# alu.net
KiCad netlist of a schematic drawn in EAGLE
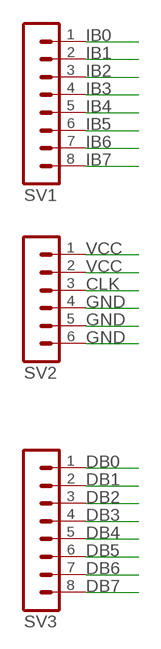
[diagram p0: schematic, sheet 1, part 1 of 2]
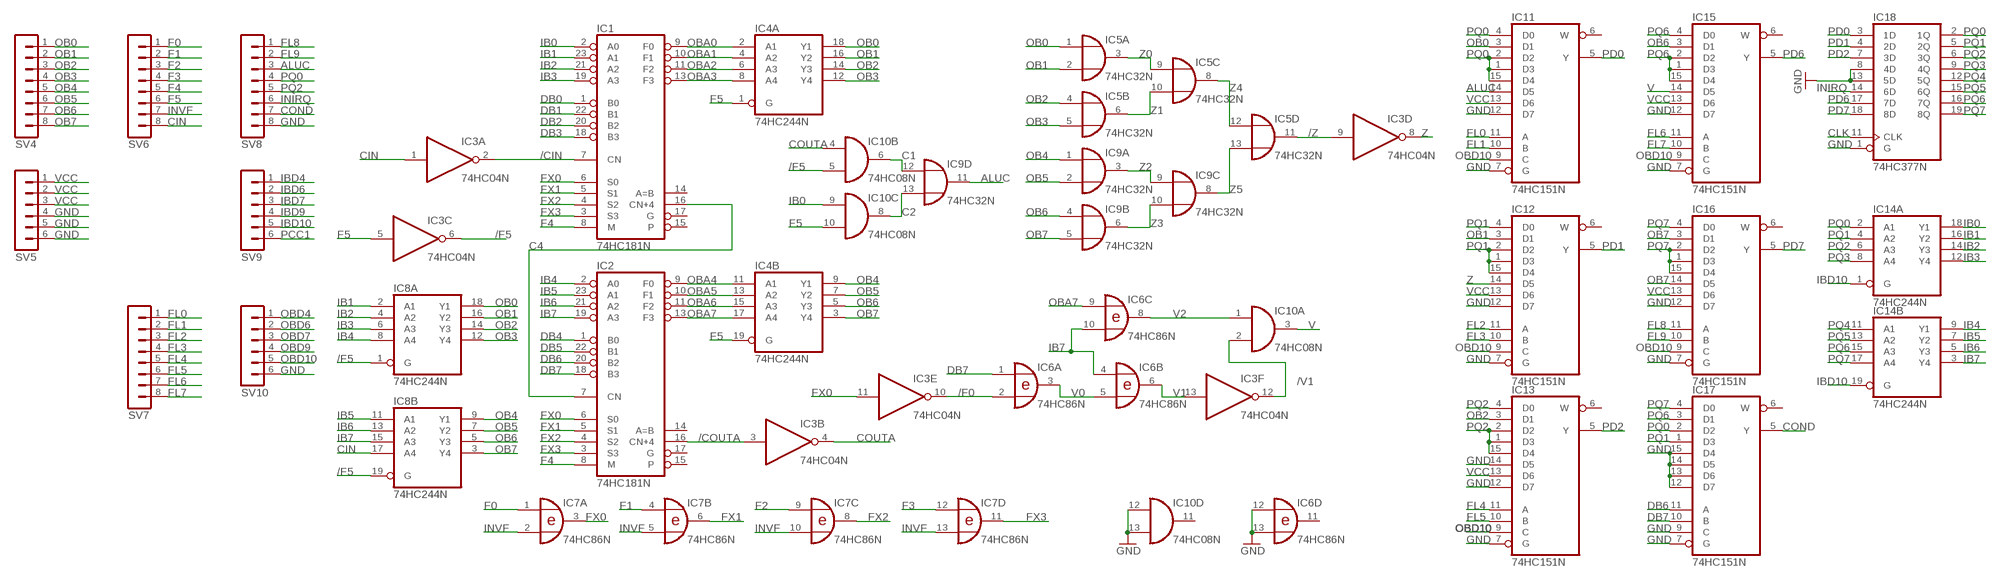
[diagram p1: schematic, sheet 1, part 2 of 2]

(export (version "E")
  (design (tool "Eeschema 10.0.6"))
  (components
    (comp (ref "IC1")
      (value "74HC181N")
      (footprint "eagle-import:DIL24-6")
      (libsource (lib "eagle-import") (part "74181NHC"))
    )
    (comp (ref "IC2")
      (value "74HC181N")
      (footprint "eagle-import:DIL24-6")
      (libsource (lib "eagle-import") (part "74181NHC"))
    )
    (comp (ref "IC3")
      (value "74HC04N")
      (footprint "eagle-import:DIL14")
      (libsource (lib "eagle-import") (part "7404NHC"))
    )
    (comp (ref "IC4")
      (value "74HC244N")
      (footprint "eagle-import:DIL20")
      (libsource (lib "eagle-import") (part "74244NHC"))
    )
    (comp (ref "IC5")
      (value "74HC32N")
      (footprint "eagle-import:DIL14")
      (libsource (lib "eagle-import") (part "7432NHC"))
    )
    (comp (ref "IC6")
      (value "74HC86N")
      (footprint "eagle-import:DIL14")
      (libsource (lib "eagle-import") (part "7486NHC"))
    )
    (comp (ref "IC7")
      (value "74HC86N")
      (footprint "eagle-import:DIL14")
      (libsource (lib "eagle-import") (part "7486NHC"))
    )
    (comp (ref "IC8")
      (value "74HC244N")
      (footprint "eagle-import:DIL20")
      (libsource (lib "eagle-import") (part "74244NHC"))
    )
    (comp (ref "IC9")
      (value "74HC32N")
      (footprint "eagle-import:DIL14")
      (libsource (lib "eagle-import") (part "7432NHC"))
    )
    (comp (ref "IC10")
      (value "74HC08N")
      (footprint "eagle-import:DIL14")
      (libsource (lib "eagle-import") (part "7408NHC"))
    )
    (comp (ref "IC11")
      (value "74HC151N")
      (footprint "eagle-import:DIL16")
      (libsource (lib "eagle-import") (part "74151NHC"))
    )
    (comp (ref "IC12")
      (value "74HC151N")
      (footprint "eagle-import:DIL16")
      (libsource (lib "eagle-import") (part "74151NHC"))
    )
    (comp (ref "IC13")
      (value "74HC151N")
      (footprint "eagle-import:DIL16")
      (libsource (lib "eagle-import") (part "74151NHC"))
    )
    (comp (ref "IC14")
      (value "74HC244N")
      (footprint "eagle-import:DIL20")
      (libsource (lib "eagle-import") (part "74244NHC"))
    )
    (comp (ref "IC15")
      (value "74HC151N")
      (footprint "eagle-import:DIL16")
      (libsource (lib "eagle-import") (part "74151NHC"))
    )
    (comp (ref "IC16")
      (value "74HC151N")
      (footprint "eagle-import:DIL16")
      (libsource (lib "eagle-import") (part "74151NHC"))
    )
    (comp (ref "IC17")
      (value "74HC151N")
      (footprint "eagle-import:DIL16")
      (libsource (lib "eagle-import") (part "74151NHC"))
    )
    (comp (ref "IC18")
      (value "74HC377N")
      (footprint "eagle-import:DIL20")
      (libsource (lib "eagle-import") (part "74377NHC"))
    )
    (comp (ref "SV1")
      (value "MA08-1")
      (footprint "eagle-import:MA08-1")
      (libsource (lib "eagle-import") (part "MA08-1"))
    )
    (comp (ref "SV2")
      (value "MA06-1")
      (footprint "eagle-import:MA06-1")
      (libsource (lib "eagle-import") (part "MA06-1"))
    )
    (comp (ref "SV3")
      (value "MA08-1")
      (footprint "eagle-import:MA08-1")
      (libsource (lib "eagle-import") (part "MA08-1"))
    )
    (comp (ref "SV4")
      (value "MA08-1")
      (footprint "eagle-import:MA08-1")
      (libsource (lib "eagle-import") (part "MA08-1"))
    )
    (comp (ref "SV5")
      (value "MA06-1")
      (footprint "eagle-import:MA06-1")
      (libsource (lib "eagle-import") (part "MA06-1"))
    )
    (comp (ref "SV6")
      (value "MA08-1")
      (footprint "eagle-import:MA08-1")
      (libsource (lib "eagle-import") (part "MA08-1"))
    )
    (comp (ref "SV7")
      (value "MA08-1")
      (footprint "eagle-import:MA08-1")
      (libsource (lib "eagle-import") (part "MA08-1"))
    )
    (comp (ref "SV8")
      (value "MA08-1")
      (footprint "eagle-import:MA08-1")
      (libsource (lib "eagle-import") (part "MA08-1"))
    )
    (comp (ref "SV9")
      (value "MA06-1")
      (footprint "eagle-import:MA06-1")
      (libsource (lib "eagle-import") (part "MA06-1"))
    )
    (comp (ref "SV10")
      (value "MA06-1")
      (footprint "eagle-import:MA06-1")
      (libsource (lib "eagle-import") (part "MA06-1"))
    )
  )
  (nets
    (net (code "1") (name "/ALUC") (class "Default")
      (node (ref "IC11") (pin "14") (pinfunction "D5_14") (pintype "input"))
      (node (ref "IC9") (pin "11") (pinfunction "O_11") (pintype "output"))
      (node (ref "SV8") (pin "3") (pinfunction "3_3") (pintype "passive"))
    )
    (net (code "2") (name "/C1") (class "Default")
      (node (ref "IC10") (pin "6") (pinfunction "O_6") (pintype "output"))
      (node (ref "IC9") (pin "12") (pinfunction "I0_12") (pintype "input"))
    )
    (net (code "3") (name "/C2") (class "Default")
      (node (ref "IC10") (pin "8") (pinfunction "O_8") (pintype "output"))
      (node (ref "IC9") (pin "13") (pinfunction "I1_13") (pintype "input"))
    )
    (net (code "4") (name "/C4") (class "Default")
      (node (ref "IC1") (pin "16") (pinfunction "CN+4_16") (pintype "output"))
      (node (ref "IC2") (pin "7") (pinfunction "CN_7") (pintype "input"))
    )
    (net (code "5") (name "/CIN") (class "Default")
      (node (ref "IC3") (pin "1") (pinfunction "I_1") (pintype "input"))
      (node (ref "IC8") (pin "17") (pinfunction "A4_17") (pintype "input"))
      (node (ref "SV6") (pin "8") (pinfunction "8_8") (pintype "passive"))
    )
    (net (code "6") (name "/CLK") (class "Default")
      (node (ref "IC18") (pin "11") (pinfunction "CLK_11") (pintype "input"))
      (node (ref "SV2") (pin "3") (pinfunction "3_3") (pintype "passive"))
    )
    (net (code "7") (name "/COND") (class "Default")
      (node (ref "IC17") (pin "5") (pinfunction "Y_5") (pintype "output"))
      (node (ref "SV8") (pin "7") (pinfunction "7_7") (pintype "passive"))
    )
    (net (code "8") (name "/COUTA") (class "Default")
      (node (ref "IC10") (pin "4") (pinfunction "I0_4") (pintype "input"))
      (node (ref "IC3") (pin "4") (pinfunction "O_4") (pintype "output"))
    )
    (net (code "9") (name "/DB0") (class "Default")
      (node (ref "IC1") (pin "1") (pinfunction "B0_1") (pintype "input"))
      (node (ref "SV3") (pin "1") (pinfunction "1_1") (pintype "passive"))
    )
    (net (code "10") (name "/DB1") (class "Default")
      (node (ref "IC1") (pin "22") (pinfunction "B1_22") (pintype "input"))
      (node (ref "SV3") (pin "2") (pinfunction "2_2") (pintype "passive"))
    )
    (net (code "11") (name "/DB2") (class "Default")
      (node (ref "IC1") (pin "20") (pinfunction "B2_20") (pintype "input"))
      (node (ref "SV3") (pin "3") (pinfunction "3_3") (pintype "passive"))
    )
    (net (code "12") (name "/DB3") (class "Default")
      (node (ref "IC1") (pin "18") (pinfunction "B3_18") (pintype "input"))
      (node (ref "SV3") (pin "4") (pinfunction "4_4") (pintype "passive"))
    )
    (net (code "13") (name "/DB4") (class "Default")
      (node (ref "IC2") (pin "1") (pinfunction "B0_1") (pintype "input"))
      (node (ref "SV3") (pin "5") (pinfunction "5_5") (pintype "passive"))
    )
    (net (code "14") (name "/DB5") (class "Default")
      (node (ref "IC2") (pin "22") (pinfunction "B1_22") (pintype "input"))
      (node (ref "SV3") (pin "6") (pinfunction "6_6") (pintype "passive"))
    )
    (net (code "15") (name "/DB6") (class "Default")
      (node (ref "IC17") (pin "11") (pinfunction "A_11") (pintype "input"))
      (node (ref "IC2") (pin "20") (pinfunction "B2_20") (pintype "input"))
      (node (ref "SV3") (pin "7") (pinfunction "7_7") (pintype "passive"))
    )
    (net (code "16") (name "/DB7") (class "Default")
      (node (ref "IC17") (pin "10") (pinfunction "B_10") (pintype "input"))
      (node (ref "IC2") (pin "18") (pinfunction "B3_18") (pintype "input"))
      (node (ref "IC6") (pin "1") (pinfunction "I0_1") (pintype "input"))
      (node (ref "SV3") (pin "8") (pinfunction "8_8") (pintype "passive"))
    )
    (net (code "17") (name "/F0") (class "Default")
      (node (ref "IC7") (pin "1") (pinfunction "I0_1") (pintype "input"))
      (node (ref "SV6") (pin "1") (pinfunction "1_1") (pintype "passive"))
    )
    (net (code "18") (name "/F1") (class "Default")
      (node (ref "IC7") (pin "4") (pinfunction "I0_4") (pintype "input"))
      (node (ref "SV6") (pin "2") (pinfunction "2_2") (pintype "passive"))
    )
    (net (code "19") (name "/F2") (class "Default")
      (node (ref "IC7") (pin "9") (pinfunction "I0_9") (pintype "input"))
      (node (ref "SV6") (pin "3") (pinfunction "3_3") (pintype "passive"))
    )
    (net (code "20") (name "/F3") (class "Default")
      (node (ref "IC7") (pin "12") (pinfunction "I0_12") (pintype "input"))
      (node (ref "SV6") (pin "4") (pinfunction "4_4") (pintype "passive"))
    )
    (net (code "21") (name "/F4") (class "Default")
      (node (ref "IC1") (pin "8") (pinfunction "M_8") (pintype "input"))
      (node (ref "IC2") (pin "8") (pinfunction "M_8") (pintype "input"))
      (node (ref "SV6") (pin "5") (pinfunction "5_5") (pintype "passive"))
    )
    (net (code "22") (name "/F5") (class "Default")
      (node (ref "IC10") (pin "10") (pinfunction "I1_10") (pintype "input"))
      (node (ref "IC3") (pin "5") (pinfunction "I_5") (pintype "input"))
      (node (ref "IC4") (pin "1") (pinfunction "G_1") (pintype "input"))
      (node (ref "IC4") (pin "19") (pinfunction "G_19") (pintype "input"))
      (node (ref "SV6") (pin "6") (pinfunction "6_6") (pintype "passive"))
    )
    (net (code "23") (name "/FL0") (class "Default")
      (node (ref "IC11") (pin "11") (pinfunction "A_11") (pintype "input"))
      (node (ref "SV7") (pin "1") (pinfunction "1_1") (pintype "passive"))
    )
    (net (code "24") (name "/FL1") (class "Default")
      (node (ref "IC11") (pin "10") (pinfunction "B_10") (pintype "input"))
      (node (ref "SV7") (pin "2") (pinfunction "2_2") (pintype "passive"))
    )
    (net (code "25") (name "/FL2") (class "Default")
      (node (ref "IC12") (pin "11") (pinfunction "A_11") (pintype "input"))
      (node (ref "SV7") (pin "3") (pinfunction "3_3") (pintype "passive"))
    )
    (net (code "26") (name "/FL3") (class "Default")
      (node (ref "IC12") (pin "10") (pinfunction "B_10") (pintype "input"))
      (node (ref "SV7") (pin "4") (pinfunction "4_4") (pintype "passive"))
    )
    (net (code "27") (name "/FL4") (class "Default")
      (node (ref "IC13") (pin "11") (pinfunction "A_11") (pintype "input"))
      (node (ref "SV7") (pin "5") (pinfunction "5_5") (pintype "passive"))
    )
    (net (code "28") (name "/FL5") (class "Default")
      (node (ref "IC13") (pin "10") (pinfunction "B_10") (pintype "input"))
      (node (ref "SV7") (pin "6") (pinfunction "6_6") (pintype "passive"))
    )
    (net (code "29") (name "/FL6") (class "Default")
      (node (ref "IC15") (pin "11") (pinfunction "A_11") (pintype "input"))
      (node (ref "SV7") (pin "7") (pinfunction "7_7") (pintype "passive"))
    )
    (net (code "30") (name "/FL7") (class "Default")
      (node (ref "IC15") (pin "10") (pinfunction "B_10") (pintype "input"))
      (node (ref "SV7") (pin "8") (pinfunction "8_8") (pintype "passive"))
    )
    (net (code "31") (name "/FL8") (class "Default")
      (node (ref "IC16") (pin "11") (pinfunction "A_11") (pintype "input"))
      (node (ref "SV8") (pin "1") (pinfunction "1_1") (pintype "passive"))
    )
    (net (code "32") (name "/FL9") (class "Default")
      (node (ref "IC16") (pin "10") (pinfunction "B_10") (pintype "input"))
      (node (ref "SV8") (pin "2") (pinfunction "2_2") (pintype "passive"))
    )
    (net (code "33") (name "/FX0") (class "Default")
      (node (ref "IC1") (pin "6") (pinfunction "S0_6") (pintype "input"))
      (node (ref "IC2") (pin "6") (pinfunction "S0_6") (pintype "input"))
      (node (ref "IC3") (pin "11") (pinfunction "I_11") (pintype "input"))
      (node (ref "IC7") (pin "3") (pinfunction "O_3") (pintype "output"))
    )
    (net (code "34") (name "/FX1") (class "Default")
      (node (ref "IC1") (pin "5") (pinfunction "S1_5") (pintype "input"))
      (node (ref "IC2") (pin "5") (pinfunction "S1_5") (pintype "input"))
      (node (ref "IC7") (pin "6") (pinfunction "O_6") (pintype "output"))
    )
    (net (code "35") (name "/FX2") (class "Default")
      (node (ref "IC1") (pin "4") (pinfunction "S2_4") (pintype "input"))
      (node (ref "IC2") (pin "4") (pinfunction "S2_4") (pintype "input"))
      (node (ref "IC7") (pin "8") (pinfunction "O_8") (pintype "output"))
    )
    (net (code "36") (name "/FX3") (class "Default")
      (node (ref "IC1") (pin "3") (pinfunction "S3_3") (pintype "input"))
      (node (ref "IC2") (pin "3") (pinfunction "S3_3") (pintype "input"))
      (node (ref "IC7") (pin "11") (pinfunction "O_11") (pintype "output"))
    )
    (net (code "37") (name "/IB0") (class "Default")
      (node (ref "IC1") (pin "2") (pinfunction "A0_2") (pintype "input"))
      (node (ref "IC10") (pin "9") (pinfunction "I0_9") (pintype "input"))
      (node (ref "IC14") (pin "18") (pinfunction "Y1_18") (pintype "tri_state"))
      (node (ref "SV1") (pin "1") (pinfunction "1_1") (pintype "passive"))
    )
    (net (code "38") (name "/IB1") (class "Default")
      (node (ref "IC1") (pin "23") (pinfunction "A1_23") (pintype "input"))
      (node (ref "IC14") (pin "16") (pinfunction "Y2_16") (pintype "tri_state"))
      (node (ref "IC8") (pin "2") (pinfunction "A1_2") (pintype "input"))
      (node (ref "SV1") (pin "2") (pinfunction "2_2") (pintype "passive"))
    )
    (net (code "39") (name "/IB2") (class "Default")
      (node (ref "IC1") (pin "21") (pinfunction "A2_21") (pintype "input"))
      (node (ref "IC14") (pin "14") (pinfunction "Y3_14") (pintype "tri_state"))
      (node (ref "IC8") (pin "4") (pinfunction "A2_4") (pintype "input"))
      (node (ref "SV1") (pin "3") (pinfunction "3_3") (pintype "passive"))
    )
    (net (code "40") (name "/IB3") (class "Default")
      (node (ref "IC1") (pin "19") (pinfunction "A3_19") (pintype "input"))
      (node (ref "IC14") (pin "12") (pinfunction "Y4_12") (pintype "tri_state"))
      (node (ref "IC8") (pin "6") (pinfunction "A3_6") (pintype "input"))
      (node (ref "SV1") (pin "4") (pinfunction "4_4") (pintype "passive"))
    )
    (net (code "41") (name "/IB4") (class "Default")
      (node (ref "IC14") (pin "9") (pinfunction "Y1_9") (pintype "tri_state"))
      (node (ref "IC2") (pin "2") (pinfunction "A0_2") (pintype "input"))
      (node (ref "IC8") (pin "8") (pinfunction "A4_8") (pintype "input"))
      (node (ref "SV1") (pin "5") (pinfunction "5_5") (pintype "passive"))
    )
    (net (code "42") (name "/IB5") (class "Default")
      (node (ref "IC14") (pin "7") (pinfunction "Y2_7") (pintype "tri_state"))
      (node (ref "IC2") (pin "23") (pinfunction "A1_23") (pintype "input"))
      (node (ref "IC8") (pin "11") (pinfunction "A1_11") (pintype "input"))
      (node (ref "SV1") (pin "6") (pinfunction "6_6") (pintype "passive"))
    )
    (net (code "43") (name "/IB6") (class "Default")
      (node (ref "IC14") (pin "5") (pinfunction "Y3_5") (pintype "tri_state"))
      (node (ref "IC2") (pin "21") (pinfunction "A2_21") (pintype "input"))
      (node (ref "IC8") (pin "13") (pinfunction "A2_13") (pintype "input"))
      (node (ref "SV1") (pin "7") (pinfunction "7_7") (pintype "passive"))
    )
    (net (code "44") (name "/IB7") (class "Default")
      (node (ref "IC14") (pin "3") (pinfunction "Y4_3") (pintype "tri_state"))
      (node (ref "IC2") (pin "19") (pinfunction "A3_19") (pintype "input"))
      (node (ref "IC6") (pin "10") (pinfunction "I1_10") (pintype "input"))
      (node (ref "IC6") (pin "4") (pinfunction "I0_4") (pintype "input"))
      (node (ref "IC8") (pin "15") (pinfunction "A3_15") (pintype "input"))
      (node (ref "SV1") (pin "8") (pinfunction "8_8") (pintype "passive"))
    )
    (net (code "45") (name "/IBD4") (class "Default")
      (node (ref "SV9") (pin "1") (pinfunction "1_1") (pintype "passive"))
    )
    (net (code "46") (name "/IBD6") (class "Default")
      (node (ref "SV9") (pin "2") (pinfunction "2_2") (pintype "passive"))
    )
    (net (code "47") (name "/IBD7") (class "Default")
      (node (ref "SV9") (pin "3") (pinfunction "3_3") (pintype "passive"))
    )
    (net (code "48") (name "/IBD9") (class "Default")
      (node (ref "SV9") (pin "4") (pinfunction "4_4") (pintype "passive"))
    )
    (net (code "49") (name "/IBD10") (class "Default")
      (node (ref "IC14") (pin "1") (pinfunction "G_1") (pintype "input"))
      (node (ref "IC14") (pin "19") (pinfunction "G_19") (pintype "input"))
      (node (ref "SV9") (pin "5") (pinfunction "5_5") (pintype "passive"))
    )
    (net (code "50") (name "/INIRQ") (class "Default")
      (node (ref "IC18") (pin "14") (pinfunction "6D_14") (pintype "input"))
      (node (ref "SV8") (pin "6") (pinfunction "6_6") (pintype "passive"))
    )
    (net (code "51") (name "/INVF") (class "Default")
      (node (ref "IC7") (pin "10") (pinfunction "I1_10") (pintype "input"))
      (node (ref "IC7") (pin "13") (pinfunction "I1_13") (pintype "input"))
      (node (ref "IC7") (pin "2") (pinfunction "I1_2") (pintype "input"))
      (node (ref "IC7") (pin "5") (pinfunction "I1_5") (pintype "input"))
      (node (ref "SV6") (pin "7") (pinfunction "7_7") (pintype "passive"))
    )
    (net (code "52") (name "/OB0") (class "Default")
      (node (ref "IC11") (pin "3") (pinfunction "D1_3") (pintype "input"))
      (node (ref "IC4") (pin "18") (pinfunction "Y1_18") (pintype "tri_state"))
      (node (ref "IC5") (pin "1") (pinfunction "I0_1") (pintype "input"))
      (node (ref "IC8") (pin "18") (pinfunction "Y1_18") (pintype "tri_state"))
      (node (ref "SV4") (pin "1") (pinfunction "1_1") (pintype "passive"))
    )
    (net (code "53") (name "/OB1") (class "Default")
      (node (ref "IC12") (pin "3") (pinfunction "D1_3") (pintype "input"))
      (node (ref "IC4") (pin "16") (pinfunction "Y2_16") (pintype "tri_state"))
      (node (ref "IC5") (pin "2") (pinfunction "I1_2") (pintype "input"))
      (node (ref "IC8") (pin "16") (pinfunction "Y2_16") (pintype "tri_state"))
      (node (ref "SV4") (pin "2") (pinfunction "2_2") (pintype "passive"))
    )
    (net (code "54") (name "/OB2") (class "Default")
      (node (ref "IC13") (pin "3") (pinfunction "D1_3") (pintype "input"))
      (node (ref "IC4") (pin "14") (pinfunction "Y3_14") (pintype "tri_state"))
      (node (ref "IC5") (pin "4") (pinfunction "I0_4") (pintype "input"))
      (node (ref "IC8") (pin "14") (pinfunction "Y3_14") (pintype "tri_state"))
      (node (ref "SV4") (pin "3") (pinfunction "3_3") (pintype "passive"))
    )
    (net (code "55") (name "/OB3") (class "Default")
      (node (ref "IC4") (pin "12") (pinfunction "Y4_12") (pintype "tri_state"))
      (node (ref "IC5") (pin "5") (pinfunction "I1_5") (pintype "input"))
      (node (ref "IC8") (pin "12") (pinfunction "Y4_12") (pintype "tri_state"))
      (node (ref "SV4") (pin "4") (pinfunction "4_4") (pintype "passive"))
    )
    (net (code "56") (name "/OB4") (class "Default")
      (node (ref "IC4") (pin "9") (pinfunction "Y1_9") (pintype "tri_state"))
      (node (ref "IC8") (pin "9") (pinfunction "Y1_9") (pintype "tri_state"))
      (node (ref "IC9") (pin "1") (pinfunction "I0_1") (pintype "input"))
      (node (ref "SV4") (pin "5") (pinfunction "5_5") (pintype "passive"))
    )
    (net (code "57") (name "/OB5") (class "Default")
      (node (ref "IC4") (pin "7") (pinfunction "Y2_7") (pintype "tri_state"))
      (node (ref "IC8") (pin "7") (pinfunction "Y2_7") (pintype "tri_state"))
      (node (ref "IC9") (pin "2") (pinfunction "I1_2") (pintype "input"))
      (node (ref "SV4") (pin "6") (pinfunction "6_6") (pintype "passive"))
    )
    (net (code "58") (name "/OB6") (class "Default")
      (node (ref "IC15") (pin "3") (pinfunction "D1_3") (pintype "input"))
      (node (ref "IC4") (pin "5") (pinfunction "Y3_5") (pintype "tri_state"))
      (node (ref "IC8") (pin "5") (pinfunction "Y3_5") (pintype "tri_state"))
      (node (ref "IC9") (pin "4") (pinfunction "I0_4") (pintype "input"))
      (node (ref "SV4") (pin "7") (pinfunction "7_7") (pintype "passive"))
    )
    (net (code "59") (name "/OB7") (class "Default")
      (node (ref "IC16") (pin "14") (pinfunction "D5_14") (pintype "input"))
      (node (ref "IC16") (pin "3") (pinfunction "D1_3") (pintype "input"))
      (node (ref "IC4") (pin "3") (pinfunction "Y4_3") (pintype "tri_state"))
      (node (ref "IC8") (pin "3") (pinfunction "Y4_3") (pintype "tri_state"))
      (node (ref "IC9") (pin "5") (pinfunction "I1_5") (pintype "input"))
      (node (ref "SV4") (pin "8") (pinfunction "8_8") (pintype "passive"))
    )
    (net (code "60") (name "/OBA0") (class "Default")
      (node (ref "IC1") (pin "9") (pinfunction "F0_9") (pintype "output"))
      (node (ref "IC4") (pin "2") (pinfunction "A1_2") (pintype "input"))
    )
    (net (code "61") (name "/OBA1") (class "Default")
      (node (ref "IC1") (pin "10") (pinfunction "F1_10") (pintype "output"))
      (node (ref "IC4") (pin "4") (pinfunction "A2_4") (pintype "input"))
    )
    (net (code "62") (name "/OBA2") (class "Default")
      (node (ref "IC1") (pin "11") (pinfunction "F2_11") (pintype "output"))
      (node (ref "IC4") (pin "6") (pinfunction "A3_6") (pintype "input"))
    )
    (net (code "63") (name "/OBA3") (class "Default")
      (node (ref "IC1") (pin "13") (pinfunction "F3_13") (pintype "output"))
      (node (ref "IC4") (pin "8") (pinfunction "A4_8") (pintype "input"))
    )
    (net (code "64") (name "/OBA4") (class "Default")
      (node (ref "IC2") (pin "9") (pinfunction "F0_9") (pintype "output"))
      (node (ref "IC4") (pin "11") (pinfunction "A1_11") (pintype "input"))
    )
    (net (code "65") (name "/OBA5") (class "Default")
      (node (ref "IC2") (pin "10") (pinfunction "F1_10") (pintype "output"))
      (node (ref "IC4") (pin "13") (pinfunction "A2_13") (pintype "input"))
    )
    (net (code "66") (name "/OBA6") (class "Default")
      (node (ref "IC2") (pin "11") (pinfunction "F2_11") (pintype "output"))
      (node (ref "IC4") (pin "15") (pinfunction "A3_15") (pintype "input"))
    )
    (net (code "67") (name "/OBA7") (class "Default")
      (node (ref "IC2") (pin "13") (pinfunction "F3_13") (pintype "output"))
      (node (ref "IC4") (pin "17") (pinfunction "A4_17") (pintype "input"))
      (node (ref "IC6") (pin "9") (pinfunction "I0_9") (pintype "input"))
    )
    (net (code "68") (name "/OBD4") (class "Default")
      (node (ref "SV10") (pin "1") (pinfunction "1_1") (pintype "passive"))
    )
    (net (code "69") (name "/OBD6") (class "Default")
      (node (ref "SV10") (pin "2") (pinfunction "2_2") (pintype "passive"))
    )
    (net (code "70") (name "/OBD7") (class "Default")
      (node (ref "SV10") (pin "3") (pinfunction "3_3") (pintype "passive"))
    )
    (net (code "71") (name "/OBD9") (class "Default")
      (node (ref "SV10") (pin "4") (pinfunction "4_4") (pintype "passive"))
    )
    (net (code "72") (name "/OBD10") (class "Default")
      (node (ref "IC11") (pin "9") (pinfunction "C_9") (pintype "input"))
      (node (ref "IC12") (pin "9") (pinfunction "C_9") (pintype "input"))
      (node (ref "IC13") (pin "9") (pinfunction "C_9") (pintype "input"))
      (node (ref "IC15") (pin "9") (pinfunction "C_9") (pintype "input"))
      (node (ref "IC16") (pin "9") (pinfunction "C_9") (pintype "input"))
      (node (ref "SV10") (pin "5") (pinfunction "5_5") (pintype "passive"))
    )
    (net (code "73") (name "/PCC1") (class "Default")
      (node (ref "SV9") (pin "6") (pinfunction "6_6") (pintype "passive"))
    )
    (net (code "74") (name "/PD0") (class "Default")
      (node (ref "IC11") (pin "5") (pinfunction "Y_5") (pintype "output"))
      (node (ref "IC18") (pin "3") (pinfunction "1D_3") (pintype "input"))
    )
    (net (code "75") (name "/PD1") (class "Default")
      (node (ref "IC12") (pin "5") (pinfunction "Y_5") (pintype "output"))
      (node (ref "IC18") (pin "4") (pinfunction "2D_4") (pintype "input"))
    )
    (net (code "76") (name "/PD2") (class "Default")
      (node (ref "IC13") (pin "5") (pinfunction "Y_5") (pintype "output"))
      (node (ref "IC18") (pin "7") (pinfunction "3D_7") (pintype "input"))
    )
    (net (code "77") (name "/PD6") (class "Default")
      (node (ref "IC15") (pin "5") (pinfunction "Y_5") (pintype "output"))
      (node (ref "IC18") (pin "17") (pinfunction "7D_17") (pintype "input"))
    )
    (net (code "78") (name "/PD7") (class "Default")
      (node (ref "IC16") (pin "5") (pinfunction "Y_5") (pintype "output"))
      (node (ref "IC18") (pin "18") (pinfunction "8D_18") (pintype "input"))
    )
    (net (code "79") (name "/PQ0") (class "Default")
      (node (ref "IC11") (pin "1") (pinfunction "D3_1") (pintype "input"))
      (node (ref "IC11") (pin "15") (pinfunction "D4_15") (pintype "input"))
      (node (ref "IC11") (pin "2") (pinfunction "D2_2") (pintype "input"))
      (node (ref "IC11") (pin "4") (pinfunction "D0_4") (pintype "input"))
      (node (ref "IC14") (pin "2") (pinfunction "A1_2") (pintype "input"))
      (node (ref "IC17") (pin "2") (pinfunction "D2_2") (pintype "input"))
      (node (ref "IC18") (pin "2") (pinfunction "1Q_2") (pintype "output"))
      (node (ref "SV8") (pin "4") (pinfunction "4_4") (pintype "passive"))
    )
    (net (code "80") (name "/PQ1") (class "Default")
      (node (ref "IC12") (pin "1") (pinfunction "D3_1") (pintype "input"))
      (node (ref "IC12") (pin "15") (pinfunction "D4_15") (pintype "input"))
      (node (ref "IC12") (pin "2") (pinfunction "D2_2") (pintype "input"))
      (node (ref "IC12") (pin "4") (pinfunction "D0_4") (pintype "input"))
      (node (ref "IC14") (pin "4") (pinfunction "A2_4") (pintype "input"))
      (node (ref "IC17") (pin "1") (pinfunction "D3_1") (pintype "input"))
      (node (ref "IC18") (pin "5") (pinfunction "2Q_5") (pintype "output"))
    )
    (net (code "81") (name "/PQ2") (class "Default")
      (node (ref "IC13") (pin "1") (pinfunction "D3_1") (pintype "input"))
      (node (ref "IC13") (pin "15") (pinfunction "D4_15") (pintype "input"))
      (node (ref "IC13") (pin "2") (pinfunction "D2_2") (pintype "input"))
      (node (ref "IC13") (pin "4") (pinfunction "D0_4") (pintype "input"))
      (node (ref "IC14") (pin "6") (pinfunction "A3_6") (pintype "input"))
      (node (ref "IC18") (pin "6") (pinfunction "3Q_6") (pintype "output"))
      (node (ref "SV8") (pin "5") (pinfunction "5_5") (pintype "passive"))
    )
    (net (code "82") (name "/PQ3") (class "Default")
      (node (ref "IC14") (pin "8") (pinfunction "A4_8") (pintype "input"))
      (node (ref "IC18") (pin "9") (pinfunction "4Q_9") (pintype "output"))
    )
    (net (code "83") (name "/PQ4") (class "Default")
      (node (ref "IC14") (pin "11") (pinfunction "A1_11") (pintype "input"))
      (node (ref "IC18") (pin "12") (pinfunction "5Q_12") (pintype "output"))
    )
    (net (code "84") (name "/PQ5") (class "Default")
      (node (ref "IC14") (pin "13") (pinfunction "A2_13") (pintype "input"))
      (node (ref "IC18") (pin "15") (pinfunction "6Q_15") (pintype "output"))
    )
    (net (code "85") (name "/PQ6") (class "Default")
      (node (ref "IC14") (pin "15") (pinfunction "A3_15") (pintype "input"))
      (node (ref "IC15") (pin "1") (pinfunction "D3_1") (pintype "input"))
      (node (ref "IC15") (pin "15") (pinfunction "D4_15") (pintype "input"))
      (node (ref "IC15") (pin "2") (pinfunction "D2_2") (pintype "input"))
      (node (ref "IC15") (pin "4") (pinfunction "D0_4") (pintype "input"))
      (node (ref "IC17") (pin "3") (pinfunction "D1_3") (pintype "input"))
      (node (ref "IC18") (pin "16") (pinfunction "7Q_16") (pintype "output"))
    )
    (net (code "86") (name "/PQ7") (class "Default")
      (node (ref "IC14") (pin "17") (pinfunction "A4_17") (pintype "input"))
      (node (ref "IC16") (pin "1") (pinfunction "D3_1") (pintype "input"))
      (node (ref "IC16") (pin "15") (pinfunction "D4_15") (pintype "input"))
      (node (ref "IC16") (pin "2") (pinfunction "D2_2") (pintype "input"))
      (node (ref "IC16") (pin "4") (pinfunction "D0_4") (pintype "input"))
      (node (ref "IC17") (pin "4") (pinfunction "D0_4") (pintype "input"))
      (node (ref "IC18") (pin "19") (pinfunction "8Q_19") (pintype "output"))
    )
    (net (code "87") (name "/V") (class "Default")
      (node (ref "IC10") (pin "3") (pinfunction "O_3") (pintype "output"))
      (node (ref "IC15") (pin "14") (pinfunction "D5_14") (pintype "input"))
    )
    (net (code "88") (name "/V0") (class "Default")
      (node (ref "IC6") (pin "3") (pinfunction "O_3") (pintype "output"))
      (node (ref "IC6") (pin "5") (pinfunction "I1_5") (pintype "input"))
    )
    (net (code "89") (name "/V1") (class "Default")
      (node (ref "IC3") (pin "13") (pinfunction "I_13") (pintype "input"))
      (node (ref "IC6") (pin "6") (pinfunction "O_6") (pintype "output"))
    )
    (net (code "90") (name "/V2") (class "Default")
      (node (ref "IC10") (pin "1") (pinfunction "I0_1") (pintype "input"))
      (node (ref "IC6") (pin "8") (pinfunction "O_8") (pintype "output"))
    )
    (net (code "91") (name "/VCC") (class "Default")
      (node (ref "IC11") (pin "13") (pinfunction "D6_13") (pintype "input"))
      (node (ref "IC12") (pin "13") (pinfunction "D6_13") (pintype "input"))
      (node (ref "IC13") (pin "13") (pinfunction "D6_13") (pintype "input"))
      (node (ref "IC15") (pin "13") (pinfunction "D6_13") (pintype "input"))
      (node (ref "IC16") (pin "13") (pinfunction "D6_13") (pintype "input"))
      (node (ref "SV2") (pin "1") (pinfunction "1_1") (pintype "passive"))
      (node (ref "SV2") (pin "2") (pinfunction "2_2") (pintype "passive"))
      (node (ref "SV5") (pin "1") (pinfunction "1_1") (pintype "passive"))
      (node (ref "SV5") (pin "2") (pinfunction "2_2") (pintype "passive"))
      (node (ref "SV5") (pin "3") (pinfunction "3_3") (pintype "passive"))
    )
    (net (code "92") (name "/Z") (class "Default")
      (node (ref "IC12") (pin "14") (pinfunction "D5_14") (pintype "input"))
      (node (ref "IC3") (pin "8") (pinfunction "O_8") (pintype "output"))
    )
    (net (code "93") (name "/Z0") (class "Default")
      (node (ref "IC5") (pin "3") (pinfunction "O_3") (pintype "output"))
      (node (ref "IC5") (pin "9") (pinfunction "I0_9") (pintype "input"))
    )
    (net (code "94") (name "/Z1") (class "Default")
      (node (ref "IC5") (pin "10") (pinfunction "I1_10") (pintype "input"))
      (node (ref "IC5") (pin "6") (pinfunction "O_6") (pintype "output"))
    )
    (net (code "95") (name "/Z2") (class "Default")
      (node (ref "IC9") (pin "3") (pinfunction "O_3") (pintype "output"))
      (node (ref "IC9") (pin "9") (pinfunction "I0_9") (pintype "input"))
    )
    (net (code "96") (name "/Z3") (class "Default")
      (node (ref "IC9") (pin "10") (pinfunction "I1_10") (pintype "input"))
      (node (ref "IC9") (pin "6") (pinfunction "O_6") (pintype "output"))
    )
    (net (code "97") (name "/Z4") (class "Default")
      (node (ref "IC5") (pin "12") (pinfunction "I0_12") (pintype "input"))
      (node (ref "IC5") (pin "8") (pinfunction "O_8") (pintype "output"))
    )
    (net (code "98") (name "/Z5") (class "Default")
      (node (ref "IC5") (pin "13") (pinfunction "I1_13") (pintype "input"))
      (node (ref "IC9") (pin "8") (pinfunction "O_8") (pintype "output"))
    )
    (net (code "99") (name "/{slash}CIN") (class "Default")
      (node (ref "IC1") (pin "7") (pinfunction "CN_7") (pintype "input"))
      (node (ref "IC3") (pin "2") (pinfunction "O_2") (pintype "output"))
    )
    (net (code "100") (name "/{slash}COUTA") (class "Default")
      (node (ref "IC2") (pin "16") (pinfunction "CN+4_16") (pintype "output"))
      (node (ref "IC3") (pin "3") (pinfunction "I_3") (pintype "input"))
    )
    (net (code "101") (name "/{slash}F0") (class "Default")
      (node (ref "IC3") (pin "10") (pinfunction "O_10") (pintype "output"))
      (node (ref "IC6") (pin "2") (pinfunction "I1_2") (pintype "input"))
    )
    (net (code "102") (name "/{slash}F5") (class "Default")
      (node (ref "IC10") (pin "5") (pinfunction "I1_5") (pintype "input"))
      (node (ref "IC3") (pin "6") (pinfunction "O_6") (pintype "output"))
      (node (ref "IC8") (pin "1") (pinfunction "G_1") (pintype "input"))
      (node (ref "IC8") (pin "19") (pinfunction "G_19") (pintype "input"))
    )
    (net (code "103") (name "/{slash}V1") (class "Default")
      (node (ref "IC10") (pin "2") (pinfunction "I1_2") (pintype "input"))
      (node (ref "IC3") (pin "12") (pinfunction "O_12") (pintype "output"))
    )
    (net (code "104") (name "/{slash}Z") (class "Default")
      (node (ref "IC3") (pin "9") (pinfunction "I_9") (pintype "input"))
      (node (ref "IC5") (pin "11") (pinfunction "O_11") (pintype "output"))
    )
    (net (code "105") (name "GND") (class "Default")
      (node (ref "IC10") (pin "12") (pinfunction "I0_12") (pintype "input"))
      (node (ref "IC10") (pin "13") (pinfunction "I1_13") (pintype "input"))
      (node (ref "IC11") (pin "12") (pinfunction "D7_12") (pintype "input"))
      (node (ref "IC11") (pin "7") (pinfunction "G_7") (pintype "input"))
      (node (ref "IC12") (pin "12") (pinfunction "D7_12") (pintype "input"))
      (node (ref "IC12") (pin "7") (pinfunction "G_7") (pintype "input"))
      (node (ref "IC13") (pin "12") (pinfunction "D7_12") (pintype "input"))
      (node (ref "IC13") (pin "14") (pinfunction "D5_14") (pintype "input"))
      (node (ref "IC13") (pin "7") (pinfunction "G_7") (pintype "input"))
      (node (ref "IC15") (pin "12") (pinfunction "D7_12") (pintype "input"))
      (node (ref "IC15") (pin "7") (pinfunction "G_7") (pintype "input"))
      (node (ref "IC16") (pin "12") (pinfunction "D7_12") (pintype "input"))
      (node (ref "IC16") (pin "7") (pinfunction "G_7") (pintype "input"))
      (node (ref "IC17") (pin "12") (pinfunction "D7_12") (pintype "input"))
      (node (ref "IC17") (pin "13") (pinfunction "D6_13") (pintype "input"))
      (node (ref "IC17") (pin "14") (pinfunction "D5_14") (pintype "input"))
      (node (ref "IC17") (pin "15") (pinfunction "D4_15") (pintype "input"))
      (node (ref "IC17") (pin "7") (pinfunction "G_7") (pintype "input"))
      (node (ref "IC17") (pin "9") (pinfunction "C_9") (pintype "input"))
      (node (ref "IC18") (pin "1") (pinfunction "G_1") (pintype "input"))
      (node (ref "IC18") (pin "13") (pinfunction "5D_13") (pintype "input"))
      (node (ref "IC18") (pin "8") (pinfunction "4D_8") (pintype "input"))
      (node (ref "IC6") (pin "12") (pinfunction "I0_12") (pintype "input"))
      (node (ref "IC6") (pin "13") (pinfunction "I1_13") (pintype "input"))
      (node (ref "SV10") (pin "6") (pinfunction "6_6") (pintype "passive"))
      (node (ref "SV2") (pin "4") (pinfunction "4_4") (pintype "passive"))
      (node (ref "SV2") (pin "5") (pinfunction "5_5") (pintype "passive"))
      (node (ref "SV2") (pin "6") (pinfunction "6_6") (pintype "passive"))
      (node (ref "SV5") (pin "4") (pinfunction "4_4") (pintype "passive"))
      (node (ref "SV5") (pin "5") (pinfunction "5_5") (pintype "passive"))
      (node (ref "SV5") (pin "6") (pinfunction "6_6") (pintype "passive"))
      (node (ref "SV8") (pin "8") (pinfunction "8_8") (pintype "passive"))
    )
    (net (code "106") (name "unconnected-(IC1A-A=B-Pad14)") (class "Default")
      (node (ref "IC1") (pin "14") (pinfunction "A=B_14") (pintype "output"))
    )
    (net (code "107") (name "unconnected-(IC1A-G-Pad17)") (class "Default")
      (node (ref "IC1") (pin "17") (pinfunction "G_17") (pintype "output"))
    )
    (net (code "108") (name "unconnected-(IC1A-P-Pad15)") (class "Default")
      (node (ref "IC1") (pin "15") (pinfunction "P_15") (pintype "output"))
    )
    (net (code "109") (name "unconnected-(IC2A-A=B-Pad14)") (class "Default")
      (node (ref "IC2") (pin "14") (pinfunction "A=B_14") (pintype "output"))
    )
    (net (code "110") (name "unconnected-(IC2A-G-Pad17)") (class "Default")
      (node (ref "IC2") (pin "17") (pinfunction "G_17") (pintype "output"))
    )
    (net (code "111") (name "unconnected-(IC2A-P-Pad15)") (class "Default")
      (node (ref "IC2") (pin "15") (pinfunction "P_15") (pintype "output"))
    )
    (net (code "112") (name "unconnected-(IC6D-O-Pad11)") (class "Default")
      (node (ref "IC6") (pin "11") (pinfunction "O_11") (pintype "output"))
    )
    (net (code "113") (name "unconnected-(IC10D-O-Pad11)") (class "Default")
      (node (ref "IC10") (pin "11") (pinfunction "O_11") (pintype "output"))
    )
    (net (code "114") (name "unconnected-(IC11A-W-Pad6)") (class "Default")
      (node (ref "IC11") (pin "6") (pinfunction "W_6") (pintype "output"))
    )
    (net (code "115") (name "unconnected-(IC12A-W-Pad6)") (class "Default")
      (node (ref "IC12") (pin "6") (pinfunction "W_6") (pintype "output"))
    )
    (net (code "116") (name "unconnected-(IC13A-W-Pad6)") (class "Default")
      (node (ref "IC13") (pin "6") (pinfunction "W_6") (pintype "output"))
    )
    (net (code "117") (name "unconnected-(IC15A-W-Pad6)") (class "Default")
      (node (ref "IC15") (pin "6") (pinfunction "W_6") (pintype "output"))
    )
    (net (code "118") (name "unconnected-(IC16A-W-Pad6)") (class "Default")
      (node (ref "IC16") (pin "6") (pinfunction "W_6") (pintype "output"))
    )
    (net (code "119") (name "unconnected-(IC17A-W-Pad6)") (class "Default")
      (node (ref "IC17") (pin "6") (pinfunction "W_6") (pintype "output"))
    )
  )
)
